# Connectors.net
KiCad netlist of a schematic drawn in Altium Designer
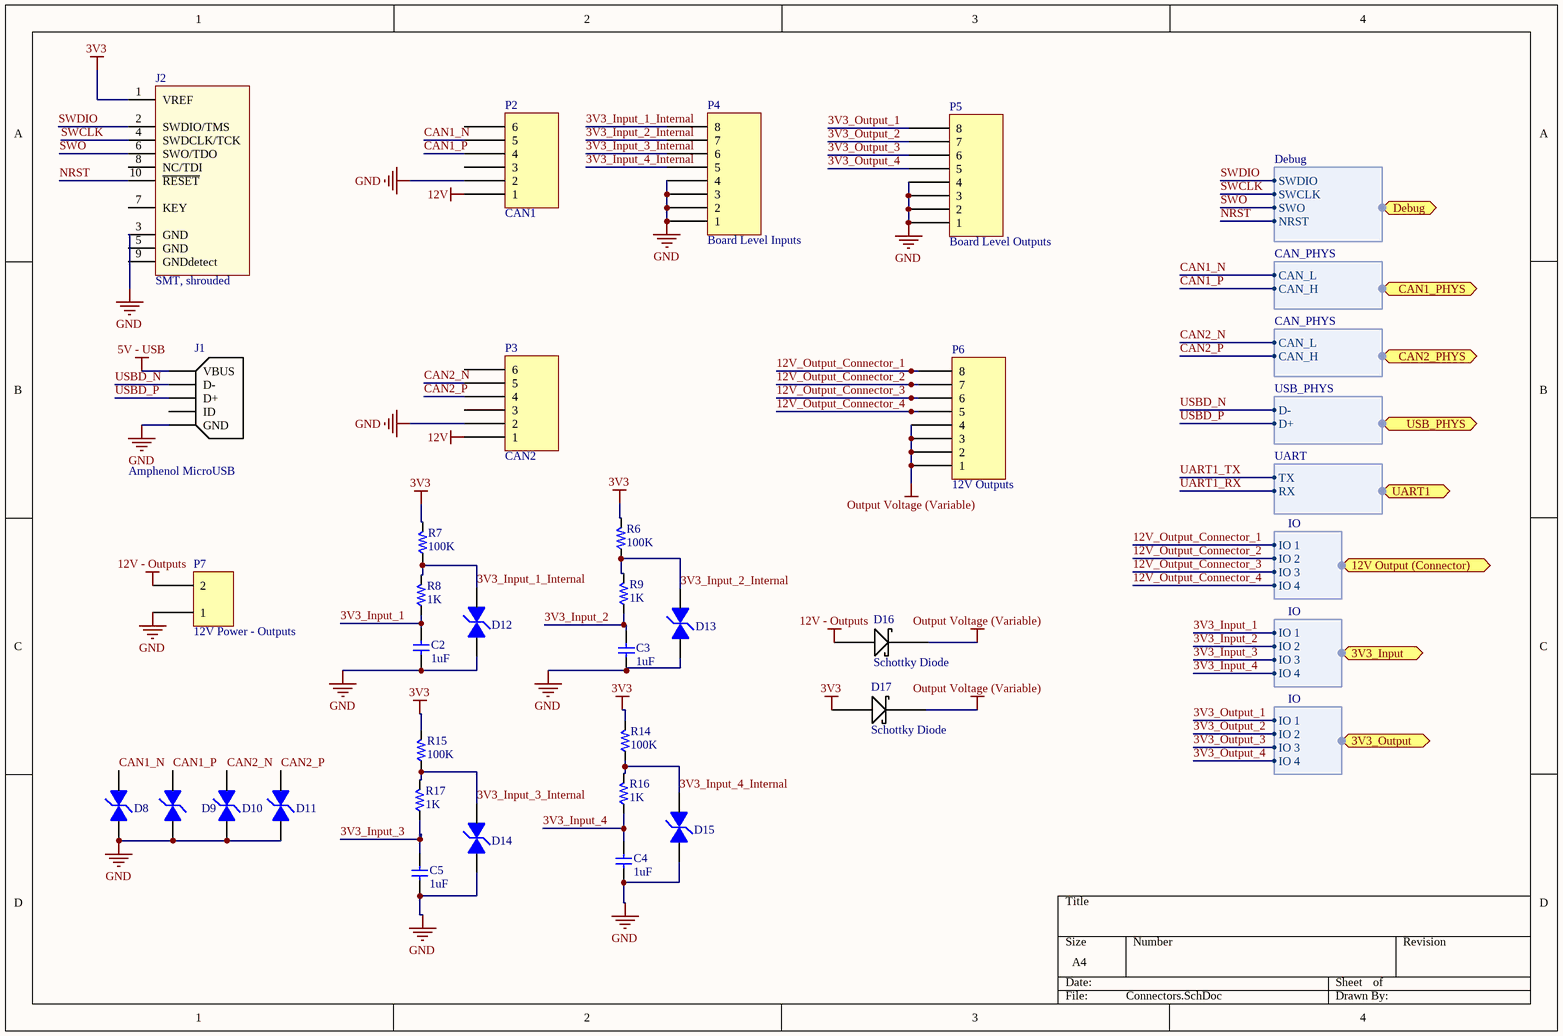
[diagram p0: Connectors.SchDoc]

(export (version "E")
  (design (tool "Eeschema 10.0.6"))
  (components
    (comp (ref "C2")
      (value "1uF")
      (footprint "PCB_GENERIC_SMD_0603")
      (description "CAP CER 0603 1uF 16V X5R 20%")
      (fields (field (name "TOLERANCE") "20%") (field (name "VOLTAGE") "16V"))
      (libsource (lib "CAP-0603") (part "C060-0001U-00"))
    )
    (comp (ref "C3")
      (value "1uF")
      (footprint "PCB_GENERIC_SMD_0603")
      (description "CAP CER 0603 1uF 16V X5R 20%")
      (fields (field (name "TOLERANCE") "20%") (field (name "VOLTAGE") "16V"))
      (libsource (lib "CAP-0603") (part "C060-0001U-00"))
    )
    (comp (ref "C4")
      (value "1uF")
      (footprint "PCB_GENERIC_SMD_0603")
      (description "CAP CER 0603 1uF 16V X5R 20%")
      (fields (field (name "TOLERANCE") "20%") (field (name "VOLTAGE") "16V"))
      (libsource (lib "CAP-0603") (part "C060-0001U-00"))
    )
    (comp (ref "C5")
      (value "1uF")
      (footprint "PCB_GENERIC_SMD_0603")
      (description "CAP CER 0603 1uF 16V X5R 20%")
      (fields (field (name "TOLERANCE") "20%") (field (name "VOLTAGE") "16V"))
      (libsource (lib "CAP-0603") (part "C060-0001U-00"))
    )
    (comp (ref "D8")
      (value "TVS Diode")
      (footprint "TVS Diode")
      (fields (field (name "MANUFACTURER") "Bourns"))
      (libsource (lib "TVS Diode") (part "TVS Diode"))
    )
    (comp (ref "D9")
      (value "TVS Diode")
      (footprint "TVS Diode")
      (fields (field (name "MANUFACTURER") "Bourns"))
      (libsource (lib "TVS Diode") (part "TVS Diode"))
    )
    (comp (ref "D10")
      (value "TVS Diode")
      (footprint "TVS Diode")
      (fields (field (name "MANUFACTURER") "Bourns"))
      (libsource (lib "TVS Diode") (part "TVS Diode"))
    )
    (comp (ref "D11")
      (value "TVS Diode")
      (footprint "TVS Diode")
      (fields (field (name "MANUFACTURER") "Bourns"))
      (libsource (lib "TVS Diode") (part "TVS Diode"))
    )
    (comp (ref "D12")
      (value "TVS Diode")
      (footprint "TVS Diode")
      (fields (field (name "MANUFACTURER") "Bourns"))
      (libsource (lib "TVS Diode") (part "TVS Diode"))
    )
    (comp (ref "D13")
      (value "TVS Diode")
      (footprint "TVS Diode")
      (fields (field (name "MANUFACTURER") "Bourns"))
      (libsource (lib "TVS Diode") (part "TVS Diode"))
    )
    (comp (ref "D14")
      (value "TVS Diode")
      (footprint "TVS Diode")
      (fields (field (name "MANUFACTURER") "Bourns"))
      (libsource (lib "TVS Diode") (part "TVS Diode"))
    )
    (comp (ref "D15")
      (value "TVS Diode")
      (footprint "TVS Diode")
      (fields (field (name "MANUFACTURER") "Bourns"))
      (libsource (lib "TVS Diode") (part "TVS Diode"))
    )
    (comp (ref "D16")
      (value "Schottky Diode")
      (footprint "ON Semi Schottky Diode - MBRM110LT1G")
      (libsource (lib "ON Semi Schottky Diode") (part "ON Semi Schottky Diode - MBRM110LT1G"))
    )
    (comp (ref "D17")
      (value "Schottky Diode")
      (footprint "ON Semi Schottky Diode - MBRM110LT1G")
      (libsource (lib "ON Semi Schottky Diode") (part "ON Semi Schottky Diode - MBRM110LT1G"))
    )
    (comp (ref "J1")
      (value "Amphenol MicroUSB")
      (footprint "Amphenol MicroUSB")
      (libsource (lib "Amphenol MicroUSB") (part "Amphenol MicroUSB - 609-4618-1-ND"))
    )
    (comp (ref "J2")
      (value "SMT, shrouded")
      (footprint "CONN-50mil-10POS-SMD")
      (description "ARM Cortex-M 10pin connector,shrouded,SMT")
      (libsource (lib "CONN-50mil-cortexM") (part "conn_0.050{dblquote}_cortexM"))
    )
    (comp (ref "P2")
      (value "CAN1")
      (footprint "Molex Microfit 3.0 3x2:PCB_MLX_MICROFIT_3X2")
      (libsource (lib "Molex Microfit 3.0 3x2") (part "SCH_MLX_MICROFIT_3X2"))
    )
    (comp (ref "P3")
      (value "CAN2")
      (footprint "Molex Microfit 3.0 3x2:PCB_MLX_MICROFIT_3X2")
      (libsource (lib "Molex Microfit 3.0 3x2") (part "SCH_MLX_MICROFIT_3X2"))
    )
    (comp (ref "P4")
      (value "Board Level Inputs")
      (footprint "Molex Microfit 3.0 4x2:PCB_MLX_MICROFIT_4X2")
      (description "Molex Microfit Connector 4x2")
      (libsource (lib "Molex Microfit 3.0 4x2") (part "SCH_MLX_MICROFIT_4X2"))
    )
    (comp (ref "P5")
      (value "Board Level Outputs")
      (footprint "Molex Microfit 3.0 4x2:PCB_MLX_MICROFIT_4X2")
      (description "Molex Microfit Connector 4x2")
      (libsource (lib "Molex Microfit 3.0 4x2") (part "SCH_MLX_MICROFIT_4X2"))
    )
    (comp (ref "P6")
      (value "12V Outputs")
      (footprint "Molex Microfit 3.0 4x2:PCB_MLX_MICROFIT_4X2")
      (description "Molex Microfit Connector 4x2")
      (libsource (lib "Molex Microfit 3.0 4x2") (part "SCH_MLX_MICROFIT_4X2"))
    )
    (comp (ref "P7")
      (value "12V Power - Outputs")
      (footprint "Molex Mini-Fit Jr 2x1")
      (libsource (lib "Molex Mini-Fit Jr 1x2") (part "Molex Mini-Fit 1x2"))
    )
    (comp (ref "R6")
      (value "100K")
      (footprint "PCB_GENERIC_SMD_0603")
      (description "RES 0603 100K 5% 63mW")
      (fields (field (name "TOLERANCE") "5%") (field (name "POWER") "63mW"))
      (libsource (lib "RES-0603") (part "R060-00104-05"))
    )
    (comp (ref "R7")
      (value "100K")
      (footprint "PCB_GENERIC_SMD_0603")
      (description "RES 0603 100K 5% 63mW")
      (fields (field (name "TOLERANCE") "5%") (field (name "POWER") "63mW"))
      (libsource (lib "RES-0603") (part "R060-00104-05"))
    )
    (comp (ref "R8")
      (value "1K")
      (footprint "PCB_GENERIC_SMD_0603")
      (description "RES 0603 1K 5% 63mW")
      (fields (field (name "TOLERANCE") "5%") (field (name "POWER") "63mW"))
      (libsource (lib "RES-0603") (part "R060-00102-05"))
    )
    (comp (ref "R9")
      (value "1K")
      (footprint "PCB_GENERIC_SMD_0603")
      (description "RES 0603 1K 5% 63mW")
      (fields (field (name "TOLERANCE") "5%") (field (name "POWER") "63mW"))
      (libsource (lib "RES-0603") (part "R060-00102-05"))
    )
    (comp (ref "R14")
      (value "100K")
      (footprint "PCB_GENERIC_SMD_0603")
      (description "RES 0603 100K 5% 63mW")
      (fields (field (name "TOLERANCE") "5%") (field (name "POWER") "63mW"))
      (libsource (lib "RES-0603") (part "R060-00104-05"))
    )
    (comp (ref "R15")
      (value "100K")
      (footprint "PCB_GENERIC_SMD_0603")
      (description "RES 0603 100K 5% 63mW")
      (fields (field (name "TOLERANCE") "5%") (field (name "POWER") "63mW"))
      (libsource (lib "RES-0603") (part "R060-00104-05"))
    )
    (comp (ref "R16")
      (value "1K")
      (footprint "PCB_GENERIC_SMD_0603")
      (description "RES 0603 1K 5% 63mW")
      (fields (field (name "TOLERANCE") "5%") (field (name "POWER") "63mW"))
      (libsource (lib "RES-0603") (part "R060-00102-05"))
    )
    (comp (ref "R17")
      (value "1K")
      (footprint "PCB_GENERIC_SMD_0603")
      (description "RES 0603 1K 5% 63mW")
      (fields (field (name "TOLERANCE") "5%") (field (name "POWER") "63mW"))
      (libsource (lib "RES-0603") (part "R060-00102-05"))
    )
  )
  (nets
    (net (code "6") (name "/3V3_Input_1") (class "Default")
      (node (ref "C2") (pin "2") (pinfunction "2_2") (pintype "passive"))
      (node (ref "R8") (pin "1") (pinfunction "1_1") (pintype "passive"))
    )
    (net (code "7") (name "/3V3_Input_1_Internal") (class "Default")
      (node (ref "D12") (pin "1") (pintype "passive"))
      (node (ref "P4") (pin "8") (pinfunction "8_8") (pintype "passive"))
      (node (ref "R7") (pin "1") (pinfunction "1_1") (pintype "passive"))
      (node (ref "R8") (pin "2") (pinfunction "2_2") (pintype "passive"))
    )
    (net (code "8") (name "/3V3_Input_2") (class "Default")
      (node (ref "C3") (pin "2") (pinfunction "2_2") (pintype "passive"))
      (node (ref "R9") (pin "1") (pinfunction "1_1") (pintype "passive"))
    )
    (net (code "9") (name "/3V3_Input_2_Internal") (class "Default")
      (node (ref "D13") (pin "1") (pintype "passive"))
      (node (ref "P4") (pin "7") (pinfunction "7_7") (pintype "passive"))
      (node (ref "R6") (pin "1") (pinfunction "1_1") (pintype "passive"))
      (node (ref "R9") (pin "2") (pinfunction "2_2") (pintype "passive"))
    )
    (net (code "10") (name "/3V3_Input_3") (class "Default")
      (node (ref "C5") (pin "2") (pinfunction "2_2") (pintype "passive"))
      (node (ref "R17") (pin "1") (pinfunction "1_1") (pintype "passive"))
    )
    (net (code "11") (name "/3V3_Input_3_Internal") (class "Default")
      (node (ref "D14") (pin "1") (pintype "passive"))
      (node (ref "P4") (pin "6") (pinfunction "6_6") (pintype "passive"))
      (node (ref "R15") (pin "1") (pinfunction "1_1") (pintype "passive"))
      (node (ref "R17") (pin "2") (pinfunction "2_2") (pintype "passive"))
    )
    (net (code "12") (name "/3V3_Input_4") (class "Default")
      (node (ref "C4") (pin "2") (pinfunction "2_2") (pintype "passive"))
      (node (ref "R16") (pin "1") (pinfunction "1_1") (pintype "passive"))
    )
    (net (code "13") (name "/3V3_Input_4_Internal") (class "Default")
      (node (ref "D15") (pin "1") (pintype "passive"))
      (node (ref "P4") (pin "5") (pinfunction "5_5") (pintype "passive"))
      (node (ref "R14") (pin "1") (pinfunction "1_1") (pintype "passive"))
      (node (ref "R16") (pin "2") (pinfunction "2_2") (pintype "passive"))
    )
    (net (code "14") (name "/3V3_Output_1") (class "Default")
      (node (ref "P5") (pin "8") (pinfunction "8_8") (pintype "passive"))
    )
    (net (code "15") (name "/3V3_Output_2") (class "Default")
      (node (ref "P5") (pin "7") (pinfunction "7_7") (pintype "passive"))
    )
    (net (code "16") (name "/3V3_Output_3") (class "Default")
      (node (ref "P5") (pin "6") (pinfunction "6_6") (pintype "passive"))
    )
    (net (code "17") (name "/3V3_Output_4") (class "Default")
      (node (ref "P5") (pin "5") (pinfunction "5_5") (pintype "passive"))
    )
    (net (code "18") (name "/12V_Output_Connector_1") (class "Default")
      (node (ref "P6") (pin "8") (pinfunction "8_8") (pintype "passive"))
    )
    (net (code "19") (name "/12V_Output_Connector_2") (class "Default")
      (node (ref "P6") (pin "7") (pinfunction "7_7") (pintype "passive"))
    )
    (net (code "20") (name "/12V_Output_Connector_3") (class "Default")
      (node (ref "P6") (pin "6") (pinfunction "6_6") (pintype "passive"))
    )
    (net (code "21") (name "/12V_Output_Connector_4") (class "Default")
      (node (ref "P6") (pin "5") (pinfunction "5_5") (pintype "passive"))
    )
    (net (code "22") (name "/CAN1_N") (class "Default")
      (node (ref "D8") (pin "1") (pintype "passive"))
      (node (ref "P2") (pin "5") (pinfunction "5_5") (pintype "passive"))
    )
    (net (code "23") (name "/CAN1_P") (class "Default")
      (node (ref "D9") (pin "1") (pintype "passive"))
      (node (ref "P2") (pin "4") (pinfunction "4_4") (pintype "passive"))
    )
    (net (code "24") (name "/CAN2_N") (class "Default")
      (node (ref "D10") (pin "1") (pintype "passive"))
      (node (ref "P3") (pin "5") (pinfunction "5_5") (pintype "passive"))
    )
    (net (code "25") (name "/CAN2_P") (class "Default")
      (node (ref "D11") (pin "1") (pintype "passive"))
      (node (ref "P3") (pin "4") (pinfunction "4_4") (pintype "passive"))
    )
    (net (code "26") (name "/NRST") (class "Default")
      (node (ref "J2") (pin "10") (pinfunction "~{RESET}_10") (pintype "passive"))
    )
    (net (code "27") (name "/SWCLK") (class "Default")
      (node (ref "J2") (pin "4") (pinfunction "SWDCLK/TCK_4") (pintype "passive"))
    )
    (net (code "28") (name "/SWDIO") (class "Default")
      (node (ref "J2") (pin "2") (pinfunction "SWDIO/TMS_2") (pintype "passive"))
    )
    (net (code "29") (name "/SWO") (class "Default")
      (node (ref "J2") (pin "6") (pinfunction "SWO/TDO_6") (pintype "passive"))
    )
    (net (code "32") (name "/USBD_N") (class "Default")
      (node (ref "J1") (pin "2") (pinfunction "D-_2") (pintype "passive"))
    )
    (net (code "33") (name "/USBD_P") (class "Default")
      (node (ref "J1") (pin "3") (pinfunction "D+_3") (pintype "passive"))
    )
    (net (code "39") (name "3V3") (class "Default")
      (node (ref "D17") (pin "2") (pinfunction "2_2") (pintype "passive"))
      (node (ref "J2") (pin "1") (pinfunction "VREF_1") (pintype "passive"))
      (node (ref "R14") (pin "2") (pinfunction "2_2") (pintype "passive"))
      (node (ref "R15") (pin "2") (pinfunction "2_2") (pintype "passive"))
      (node (ref "R6") (pin "2") (pinfunction "2_2") (pintype "passive"))
      (node (ref "R7") (pin "2") (pinfunction "2_2") (pintype "passive"))
    )
    (net (code "40") (name "5V - USB") (class "Default")
      (node (ref "J1") (pin "1") (pinfunction "VBUS_1") (pintype "passive"))
    )
    (net (code "41") (name "12V") (class "Default")
      (node (ref "P2") (pin "1") (pinfunction "1_1") (pintype "passive"))
      (node (ref "P3") (pin "1") (pinfunction "1_1") (pintype "passive"))
    )
    (net (code "42") (name "12V - Outputs") (class "Default")
      (node (ref "D16") (pin "2") (pinfunction "2_2") (pintype "passive"))
      (node (ref "P7") (pin "2") (pinfunction "2_2") (pintype "passive"))
    )
    (net (code "43") (name "GND") (class "Default")
      (node (ref "C2") (pin "1") (pinfunction "1_1") (pintype "passive"))
      (node (ref "C3") (pin "1") (pinfunction "1_1") (pintype "passive"))
      (node (ref "C4") (pin "1") (pinfunction "1_1") (pintype "passive"))
      (node (ref "C5") (pin "1") (pinfunction "1_1") (pintype "passive"))
      (node (ref "D10") (pin "2") (pintype "passive"))
      (node (ref "D11") (pin "2") (pintype "passive"))
      (node (ref "D12") (pin "2") (pintype "passive"))
      (node (ref "D13") (pin "2") (pintype "passive"))
      (node (ref "D14") (pin "2") (pintype "passive"))
      (node (ref "D15") (pin "2") (pintype "passive"))
      (node (ref "D8") (pin "2") (pintype "passive"))
      (node (ref "D9") (pin "2") (pintype "passive"))
      (node (ref "J1") (pin "5") (pinfunction "GND_5") (pintype "passive"))
      (node (ref "J2") (pin "3") (pinfunction "GND_3") (pintype "passive"))
      (node (ref "P2") (pin "2") (pinfunction "2_2") (pintype "passive"))
      (node (ref "P3") (pin "2") (pinfunction "2_2") (pintype "passive"))
      (node (ref "P4") (pin "1") (pinfunction "1_1") (pintype "passive"))
      (node (ref "P4") (pin "2") (pinfunction "2_2") (pintype "passive"))
      (node (ref "P4") (pin "3") (pinfunction "3_3") (pintype "passive"))
      (node (ref "P4") (pin "4") (pinfunction "4_4") (pintype "passive"))
      (node (ref "P5") (pin "1") (pinfunction "1_1") (pintype "passive"))
      (node (ref "P5") (pin "2") (pinfunction "2_2") (pintype "passive"))
      (node (ref "P5") (pin "3") (pinfunction "3_3") (pintype "passive"))
      (node (ref "P5") (pin "4") (pinfunction "4_4") (pintype "passive"))
      (node (ref "P7") (pin "1") (pinfunction "1_1") (pintype "passive"))
    )
    (net (code "44") (name "Output Voltage (Variable)") (class "Default")
      (node (ref "D16") (pin "1") (pinfunction "1_1") (pintype "passive"))
      (node (ref "D17") (pin "1") (pinfunction "1_1") (pintype "passive"))
      (node (ref "P6") (pin "1") (pinfunction "1_1") (pintype "passive"))
      (node (ref "P6") (pin "2") (pinfunction "2_2") (pintype "passive"))
      (node (ref "P6") (pin "3") (pinfunction "3_3") (pintype "passive"))
      (node (ref "P6") (pin "4") (pinfunction "4_4") (pintype "passive"))
    )
    (net (code "45") (name "unconnected-(J1-ID-Pad4)") (class "Default")
      (node (ref "J1") (pin "4") (pinfunction "ID_4") (pintype "passive"))
    )
    (net (code "46") (name "unconnected-(J2-GND-Pad5)") (class "Default")
      (node (ref "J2") (pin "5") (pinfunction "GND_5") (pintype "passive"))
    )
    (net (code "47") (name "unconnected-(J2-GNDdetect-Pad9)") (class "Default")
      (node (ref "J2") (pin "9") (pinfunction "GNDdetect_9") (pintype "passive"))
    )
    (net (code "48") (name "unconnected-(J2-KEY-Pad7)") (class "Default")
      (node (ref "J2") (pin "7") (pinfunction "KEY_7") (pintype "passive"))
    )
    (net (code "49") (name "unconnected-(J2-NC{slash}TDI-Pad8)") (class "Default")
      (node (ref "J2") (pin "8") (pinfunction "NC/TDI_8") (pintype "passive"))
    )
    (net (code "50") (name "unconnected-(P2-Pad3)") (class "Default")
      (node (ref "P2") (pin "3") (pinfunction "3_3") (pintype "passive"))
    )
    (net (code "51") (name "unconnected-(P2-Pad6)") (class "Default")
      (node (ref "P2") (pin "6") (pinfunction "6_6") (pintype "passive"))
    )
    (net (code "52") (name "unconnected-(P3-Pad3)") (class "Default")
      (node (ref "P3") (pin "3") (pinfunction "3_3") (pintype "passive"))
    )
    (net (code "53") (name "unconnected-(P3-Pad6)") (class "Default")
      (node (ref "P3") (pin "6") (pinfunction "6_6") (pintype "passive"))
    )
  )
)
